# Sheet1.net
KiCad netlist of a schematic drawn in Altium Designer
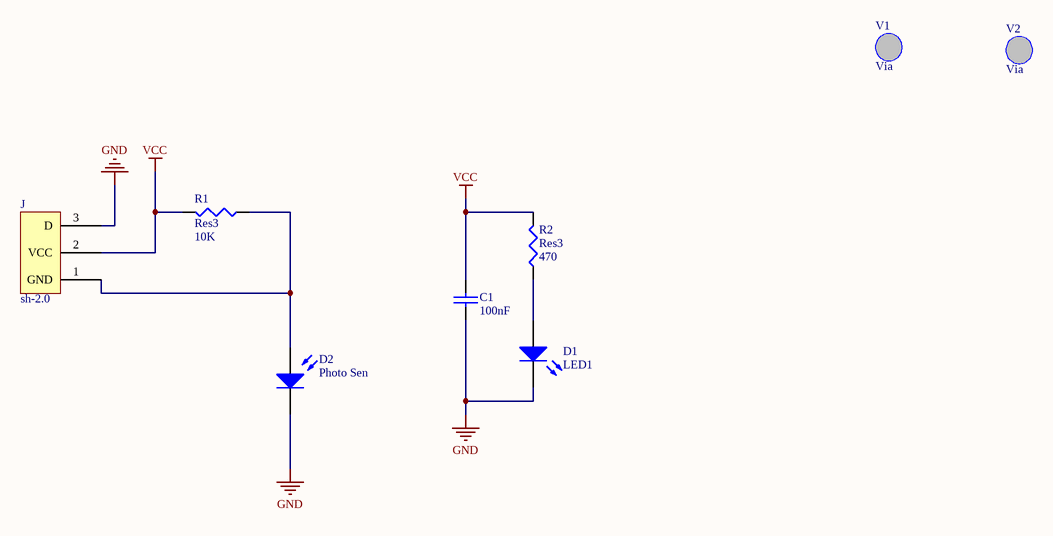
[diagram p0: Sheet1.SchDoc]

(export (version "E")
  (design (tool "Eeschema 10.0.6"))
  (components
    (comp (ref "C1")
      (value "100nF")
      (footprint "Miscellaneous Devices:1608[0603]")
      (libsource (lib "PEI_SCH") (part "CAP"))
    )
    (comp (ref "D1")
      (value "LED1")
      (footprint "zhangchong:LED")
      (description "Typical RED GaAs LED")
      (fields (field (name "PUBLISHER") "Altium Limited"))
      (libsource (lib "Miscellaneous Devices") (part "LED1"))
    )
    (comp (ref "D2")
      (value "Photo Sen")
      (footprint "zhangchong:Q")
      (description "Photosensitive Diode")
      (fields (field (name "PUBLISHER") "Altium Limited"))
      (libsource (lib "Miscellaneous Devices") (part "Photo Sen"))
    )
    (comp (ref "J") (value "sh-2.0") (footprint "sh-2.0") (libsource (lib "zhaoyujiu") (part "sh-2.0")))
    (comp (ref "R1")
      (value "Res3")
      (footprint "Miscellaneous Devices:1608[0603]")
      (description "Resistor")
      (fields (field (name "ALTIUM_VALUE") "10K") (field (name "PUBLISHER") "Altium Limited"))
      (libsource (lib "Miscellaneous Devices") (part "Res3"))
    )
    (comp (ref "R2")
      (value "Res3")
      (footprint "Miscellaneous Devices:1608[0603]")
      (description "Resistor")
      (fields (field (name "ALTIUM_VALUE") "470") (field (name "PUBLISHER") "Altium Limited"))
      (libsource (lib "Miscellaneous Devices") (part "Res3"))
    )
    (comp (ref "V1") (value "Via") (footprint "zhangchong:Via") (libsource (lib "zhangchong") (part "Via")))
    (comp (ref "V2") (value "Via") (footprint "zhangchong:Via") (libsource (lib "zhangchong") (part "Via")))
  )
  (nets
    (net (code "1") (name "GND") (class "Default")
      (node (ref "C1") (pin "2") (pinfunction "2_2") (pintype "passive"))
      (node (ref "D1") (pin "2") (pinfunction "K_2") (pintype "passive"))
      (node (ref "D2") (pin "2") (pinfunction "K_2") (pintype "passive"))
      (node (ref "J") (pin "3") (pinfunction "D_3") (pintype "passive"))
    )
    (net (code "2") (name "Net-(D1-A)") (class "Default")
      (node (ref "D1") (pin "1") (pinfunction "A_1") (pintype "passive"))
      (node (ref "R2") (pin "1") (pinfunction "1_1") (pintype "passive"))
    )
    (net (code "3") (name "Net-(D2-A)") (class "Default")
      (node (ref "D2") (pin "1") (pinfunction "A_1") (pintype "passive"))
      (node (ref "J") (pin "1") (pinfunction "GND_1") (pintype "passive"))
      (node (ref "R1") (pin "1") (pinfunction "1_1") (pintype "passive"))
    )
    (net (code "4") (name "VCC") (class "Default")
      (node (ref "C1") (pin "1") (pinfunction "1_1") (pintype "passive"))
      (node (ref "J") (pin "2") (pinfunction "VCC_2") (pintype "passive"))
      (node (ref "R1") (pin "2") (pinfunction "2_2") (pintype "passive"))
      (node (ref "R2") (pin "2") (pinfunction "2_2") (pintype "passive"))
    )
  )
)
